# AM-24bit-ADS1231.net
KiCad netlist of a schematic drawn in EAGLE
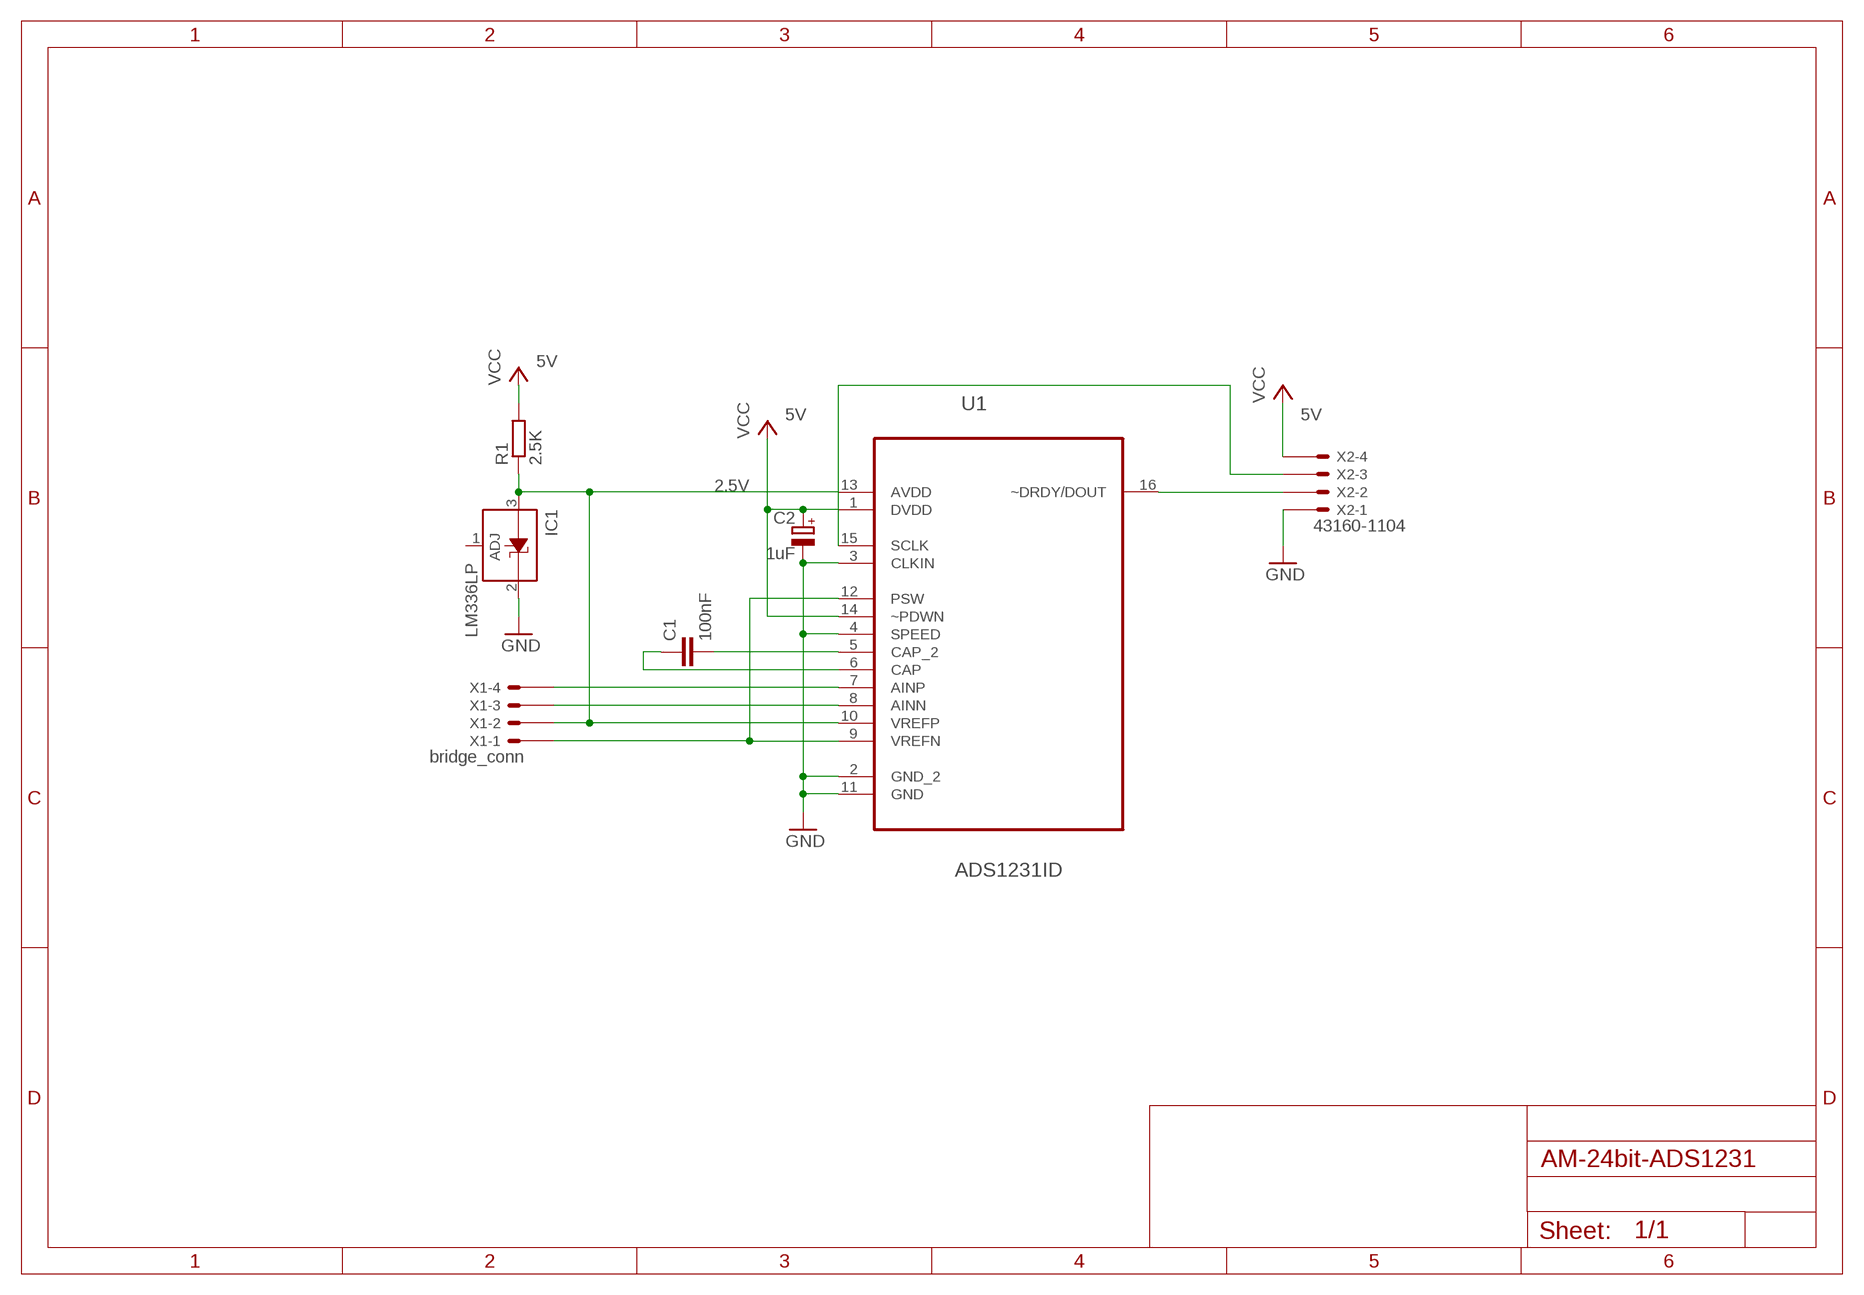
[diagram p0: schematic, sheet 1]

(export (version "E")
  (design (tool "Eeschema 10.0.6"))
  (components
    (comp (ref "C1")
      (value "100nF")
      (footprint "eagle-import:C1206K")
      (libsource (lib "eagle-import") (part "C-EUC1206K"))
    )
    (comp (ref "C2")
      (value "1uF")
      (footprint "eagle-import:153CLV-0505")
      (libsource (lib "eagle-import") (part "CPOL-EU153CLV-0505"))
    )
    (comp (ref "IC1")
      (value "LM336LP")
      (footprint "eagle-import:TO92")
      (libsource (lib "eagle-import") (part "LM336LP"))
    )
    (comp (ref "R1")
      (value "2.5K")
      (footprint "eagle-import:R3225W")
      (libsource (lib "eagle-import") (part "R-EU_R3225W"))
    )
    (comp (ref "U1")
      (value "ADS1231ID")
      (footprint "eagle-import:SOIC127P600X175-16N")
      (libsource (lib "eagle-import") (part "ADS1231ID"))
    )
    (comp (ref "X1")
      (value "bridge_conn")
      (footprint "eagle-import:43160-XX04")
      (fields (field (name "MF") "WALDOM/MOLEX") (field (name "MPN") "43160-1104"))
      (libsource (lib "eagle-import") (part "43160-0411"))
    )
    (comp (ref "X2")
      (value "43160-1104")
      (footprint "eagle-import:43160-XX04")
      (fields (field (name "MF") "WALDOM/MOLEX"))
      (libsource (lib "eagle-import") (part "43160-0411"))
    )
  )
  (nets
    (net (code "1") (name "/2.5V") (class "Default")
      (node (ref "IC1") (pin "3") (pinfunction "A_3") (pintype "input"))
      (node (ref "R1") (pin "1") (pinfunction "1_1") (pintype "passive"))
      (node (ref "U1") (pin "10") (pinfunction "VREFP_10") (pintype "input"))
      (node (ref "U1") (pin "13") (pinfunction "AVDD_13") (pintype "power_in"))
      (node (ref "X1") (pin "2@1") (pinfunction "S_2@1") (pintype "passive"))
    )
    (net (code "2") (name "GND") (class "Default")
      (node (ref "C2") (pin "-") (pinfunction "-_-") (pintype "passive"))
      (node (ref "IC1") (pin "2") (pinfunction "C_2") (pintype "passive"))
      (node (ref "U1") (pin "11") (pinfunction "GND_11") (pintype "passive"))
      (node (ref "U1") (pin "2") (pinfunction "GND_2_2") (pintype "passive"))
      (node (ref "U1") (pin "3") (pinfunction "CLKIN_3") (pintype "input"))
      (node (ref "U1") (pin "4") (pinfunction "SPEED_4") (pintype "input"))
      (node (ref "X2") (pin "1@1") (pinfunction "S_1@1") (pintype "passive"))
    )
    (net (code "3") (name "Net-(U1-AINN)") (class "Default")
      (node (ref "U1") (pin "8") (pinfunction "AINN_8") (pintype "input"))
      (node (ref "X1") (pin "3@1") (pinfunction "S_3@1") (pintype "passive"))
    )
    (net (code "4") (name "Net-(U1-AINP)") (class "Default")
      (node (ref "U1") (pin "7") (pinfunction "AINP_7") (pintype "input"))
      (node (ref "X1") (pin "4@1") (pinfunction "S_4@1") (pintype "passive"))
    )
    (net (code "5") (name "Net-(U1-CAP)") (class "Default")
      (node (ref "C1") (pin "1") (pinfunction "1_1") (pintype "passive"))
      (node (ref "U1") (pin "6") (pinfunction "CAP_6") (pintype "input"))
    )
    (net (code "6") (name "Net-(U1-CAP_2)") (class "Default")
      (node (ref "C1") (pin "2") (pinfunction "2_2") (pintype "passive"))
      (node (ref "U1") (pin "5") (pinfunction "CAP_2_5") (pintype "input"))
    )
    (net (code "7") (name "Net-(U1-PSW)") (class "Default")
      (node (ref "U1") (pin "12") (pinfunction "PSW_12") (pintype "input"))
      (node (ref "U1") (pin "9") (pinfunction "VREFN_9") (pintype "input"))
      (node (ref "X1") (pin "1@1") (pinfunction "S_1@1") (pintype "passive"))
    )
    (net (code "8") (name "Net-(U1-SCLK)") (class "Default")
      (node (ref "U1") (pin "15") (pinfunction "SCLK_15") (pintype "input"))
      (node (ref "X2") (pin "3@1") (pinfunction "S_3@1") (pintype "passive"))
    )
    (net (code "9") (name "Net-(U1-~{DRDY{slash}DOUT})") (class "Default")
      (node (ref "U1") (pin "16") (pinfunction "~{DRDY/DOUT}_16") (pintype "output"))
      (node (ref "X2") (pin "2@1") (pinfunction "S_2@1") (pintype "passive"))
    )
    (net (code "10") (name "VCC") (class "Default")
      (node (ref "C2") (pin "+") (pinfunction "+_+") (pintype "passive"))
      (node (ref "R1") (pin "2") (pinfunction "2_2") (pintype "passive"))
      (node (ref "U1") (pin "1") (pinfunction "DVDD_1") (pintype "power_in"))
      (node (ref "U1") (pin "14") (pinfunction "~{PDWN}_14") (pintype "input"))
      (node (ref "X2") (pin "4@1") (pinfunction "S_4@1") (pintype "passive"))
    )
    (net (code "11") (name "unconnected-(IC1-ADJ-Pad1)") (class "Default")
      (node (ref "IC1") (pin "1") (pinfunction "ADJ_1") (pintype "input"))
    )
    (net (code "12") (name "unconnected-(X1A-S-Pad1@2)") (class "Default")
      (node (ref "X1") (pin "1@2") (pinfunction "S_1@2") (pintype "passive"))
    )
    (net (code "13") (name "unconnected-(X1B-S-Pad2@2)") (class "Default")
      (node (ref "X1") (pin "2@2") (pinfunction "S_2@2") (pintype "passive"))
    )
    (net (code "14") (name "unconnected-(X1C-S-Pad3@2)") (class "Default")
      (node (ref "X1") (pin "3@2") (pinfunction "S_3@2") (pintype "passive"))
    )
    (net (code "15") (name "unconnected-(X1D-S-Pad4@2)") (class "Default")
      (node (ref "X1") (pin "4@2") (pinfunction "S_4@2") (pintype "passive"))
    )
    (net (code "16") (name "unconnected-(X2A-S-Pad1@2)") (class "Default")
      (node (ref "X2") (pin "1@2") (pinfunction "S_1@2") (pintype "passive"))
    )
    (net (code "17") (name "unconnected-(X2B-S-Pad2@2)") (class "Default")
      (node (ref "X2") (pin "2@2") (pinfunction "S_2@2") (pintype "passive"))
    )
    (net (code "18") (name "unconnected-(X2C-S-Pad3@2)") (class "Default")
      (node (ref "X2") (pin "3@2") (pinfunction "S_3@2") (pintype "passive"))
    )
    (net (code "19") (name "unconnected-(X2D-S-Pad4@2)") (class "Default")
      (node (ref "X2") (pin "4@2") (pinfunction "S_4@2") (pintype "passive"))
    )
  )
)
